# GPS_Shield.net
KiCad netlist of a schematic drawn in EAGLE
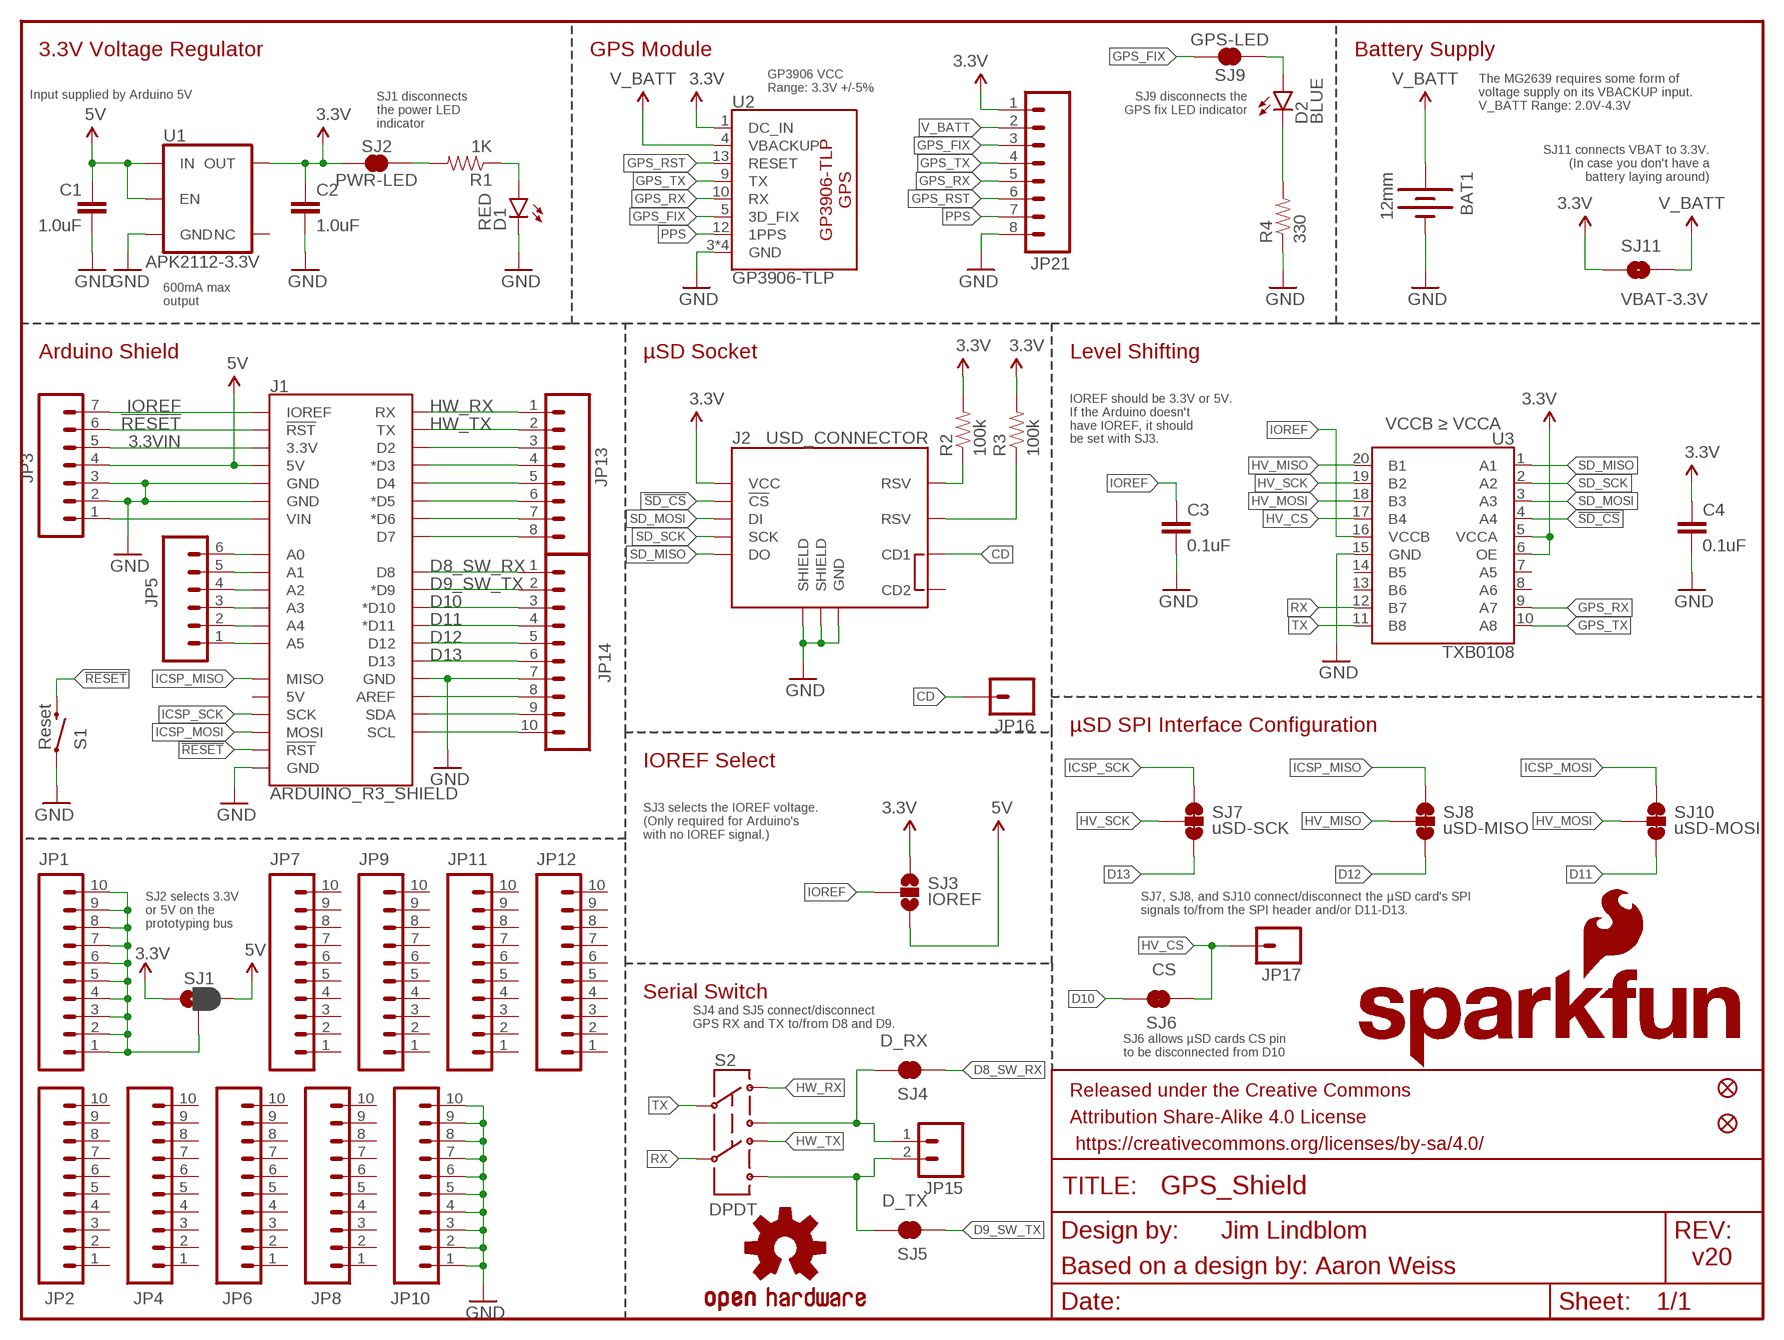
[diagram p0: schematic, sheet 1]

(export (version "E")
  (design (tool "Eeschema 10.0.6"))
  (components
    (comp (ref "BAT1")
      (value "12mm")
      (footprint "eagle-import:BATTCON_12MM")
      (libsource (lib "eagle-import") (part "BATTERY12MM"))
    )
    (comp (ref "C1")
      (value "1.0uF")
      (footprint "eagle-import:0603-CAP")
      (libsource (lib "eagle-import") (part "1.0UF-16V-10%(0603)"))
    )
    (comp (ref "C2")
      (value "1.0uF")
      (footprint "eagle-import:0603-CAP")
      (libsource (lib "eagle-import") (part "1.0UF-16V-10%(0603)"))
    )
    (comp (ref "C3")
      (value "0.1uF")
      (footprint "eagle-import:0603-CAP")
      (libsource (lib "eagle-import") (part "0.1UF-25V(+80/-20%)(0603)"))
    )
    (comp (ref "C4")
      (value "0.1uF")
      (footprint "eagle-import:0603-CAP")
      (libsource (lib "eagle-import") (part "0.1UF-25V(+80/-20%)(0603)"))
    )
    (comp (ref "D1")
      (value "RED")
      (footprint "eagle-import:LED-0603")
      (libsource (lib "eagle-import") (part "LED-RED0603"))
    )
    (comp (ref "D2")
      (value "BLUE")
      (footprint "eagle-import:LED-0603")
      (libsource (lib "eagle-import") (part "LED-BLUE0603"))
    )
    (comp (ref "FRAME1")
      (value "FRAME-LETTER")
      (footprint "eagle-import:CREATIVE_COMMONS")
      (libsource (lib "eagle-import") (part "FRAME-LETTER"))
    )
    (comp (ref "J1")
      (value "ARDUINO_R3_SHIELD")
      (footprint "eagle-import:UNO_R3_SHIELD_ICSP_NOLABELS")
      (libsource (lib "eagle-import") (part "ARDUINO_R3_SHIELD_ICSP-NO_LABELS"))
    )
    (comp (ref "J2")
      (value "USD_CONNECTOR")
      (footprint "eagle-import:MICRO-SD-SOCKET-PP")
      (libsource (lib "eagle-import") (part "USD_CONNECTOR"))
    )
    (comp (ref "JP1")
      (value "M10NO_SILK_PTH_FEMALE")
      (footprint "eagle-import:1X10_NO_SILK")
      (libsource (lib "eagle-import") (part "M10NO_SILK_PTH_FEMALE"))
    )
    (comp (ref "JP2")
      (value "M10NO_SILK_PTH_FEMALE")
      (footprint "eagle-import:1X10_NO_SILK")
      (libsource (lib "eagle-import") (part "M10NO_SILK_PTH_FEMALE"))
    )
    (comp (ref "JP3")
      (value "M07NO_SILK")
      (footprint "eagle-import:1X07_NO_SILK")
      (libsource (lib "eagle-import") (part "M07NO_SILK"))
    )
    (comp (ref "JP4")
      (value "M10NO_SILK_PTH_FEMALE")
      (footprint "eagle-import:1X10_NO_SILK")
      (libsource (lib "eagle-import") (part "M10NO_SILK_PTH_FEMALE"))
    )
    (comp (ref "JP5")
      (value "M06NO_SILK_FEMALE_PTH")
      (footprint "eagle-import:1X06_NO_SILK")
      (libsource (lib "eagle-import") (part "M06NO_SILK_FEMALE_PTH"))
    )
    (comp (ref "JP6")
      (value "M10NO_SILK_PTH_FEMALE")
      (footprint "eagle-import:1X10_NO_SILK")
      (libsource (lib "eagle-import") (part "M10NO_SILK_PTH_FEMALE"))
    )
    (comp (ref "JP7")
      (value "M10NO_SILK_PTH_FEMALE")
      (footprint "eagle-import:1X10_NO_SILK")
      (libsource (lib "eagle-import") (part "M10NO_SILK_PTH_FEMALE"))
    )
    (comp (ref "JP8")
      (value "M10NO_SILK_PTH_FEMALE")
      (footprint "eagle-import:1X10_NO_SILK")
      (libsource (lib "eagle-import") (part "M10NO_SILK_PTH_FEMALE"))
    )
    (comp (ref "JP9")
      (value "M10NO_SILK_PTH_FEMALE")
      (footprint "eagle-import:1X10_NO_SILK")
      (libsource (lib "eagle-import") (part "M10NO_SILK_PTH_FEMALE"))
    )
    (comp (ref "JP10")
      (value "M10NO_SILK_PTH_FEMALE")
      (footprint "eagle-import:1X10_NO_SILK")
      (libsource (lib "eagle-import") (part "M10NO_SILK_PTH_FEMALE"))
    )
    (comp (ref "JP11")
      (value "M10NO_SILK_PTH_FEMALE")
      (footprint "eagle-import:1X10_NO_SILK")
      (libsource (lib "eagle-import") (part "M10NO_SILK_PTH_FEMALE"))
    )
    (comp (ref "JP12")
      (value "M10NO_SILK_PTH_FEMALE")
      (footprint "eagle-import:1X10_NO_SILK")
      (libsource (lib "eagle-import") (part "M10NO_SILK_PTH_FEMALE"))
    )
    (comp (ref "JP13")
      (value "M08NO_SILK_FEMALE_PTH")
      (footprint "eagle-import:1X08_NO_SILK")
      (libsource (lib "eagle-import") (part "M08NO_SILK_FEMALE_PTH"))
    )
    (comp (ref "JP14")
      (value "M10NO_SILK_PTH_FEMALE")
      (footprint "eagle-import:1X10_NO_SILK")
      (libsource (lib "eagle-import") (part "M10NO_SILK_PTH_FEMALE"))
    )
    (comp (ref "JP15")
      (value "M021X02_NO_SILK")
      (footprint "eagle-import:1X02_NO_SILK")
      (libsource (lib "eagle-import") (part "M021X02_NO_SILK"))
    )
    (comp (ref "JP16")
      (value "M01PTH_NO_SILK_YES_STOP")
      (footprint "eagle-import:1X01_NO_SILK")
      (libsource (lib "eagle-import") (part "M01PTH_NO_SILK_YES_STOP"))
    )
    (comp (ref "JP17")
      (value "M01PTH_NO_SILK_YES_STOP")
      (footprint "eagle-import:1X01_NO_SILK")
      (libsource (lib "eagle-import") (part "M01PTH_NO_SILK_YES_STOP"))
    )
    (comp (ref "JP19")
      (value "FIDUCIAL1X2")
      (footprint "eagle-import:FIDUCIAL-1X2")
      (libsource (lib "eagle-import") (part "FIDUCIAL1X2"))
    )
    (comp (ref "JP20")
      (value "FIDUCIAL1X2")
      (footprint "eagle-import:FIDUCIAL-1X2")
      (libsource (lib "eagle-import") (part "FIDUCIAL1X2"))
    )
    (comp (ref "JP21")
      (value "M08NO_SILK_FEMALE_PTH")
      (footprint "eagle-import:1X08_NO_SILK")
      (libsource (lib "eagle-import") (part "M08NO_SILK_FEMALE_PTH"))
    )
    (comp (ref "LOGO1")
      (value "OSHW-LOGOM")
      (footprint "eagle-import:OSHW-LOGO-M")
      (libsource (lib "eagle-import") (part "OSHW-LOGOM"))
    )
    (comp (ref "LOGO2")
      (value "SFE_LOGO_NAME_FLAME.1_INCH")
      (footprint "eagle-import:SFE_LOGO_NAME_FLAME_.1")
      (libsource (lib "eagle-import") (part "SFE_LOGO_NAME_FLAME.1_INCH"))
    )
    (comp (ref "R1")
      (value "1K")
      (footprint "eagle-import:0603-RES")
      (libsource (lib "eagle-import") (part "1KOHM-1/10W-1%(0603)"))
    )
    (comp (ref "R2")
      (value "100k")
      (footprint "eagle-import:0603-RES")
      (libsource (lib "eagle-import") (part "100KOHM-1/10W-1%(0603)"))
    )
    (comp (ref "R3")
      (value "100k")
      (footprint "eagle-import:0603-RES")
      (libsource (lib "eagle-import") (part "100KOHM-1/10W-1%(0603)"))
    )
    (comp (ref "R4")
      (value "330")
      (footprint "eagle-import:0603-RES")
      (libsource (lib "eagle-import") (part "330OHM1/10W1%(0603)"))
    )
    (comp (ref "S1")
      (value "Reset")
      (footprint "eagle-import:TACTILE-SWITCH-SMD")
      (libsource (lib "eagle-import") (part "SWITCH-MOMENTARY-2SMD"))
    )
    (comp (ref "S2")
      (value "DPDT")
      (footprint "eagle-import:AYZ0202")
      (libsource (lib "eagle-import") (part "SWITCH-DPDTAYZ0202"))
    )
    (comp (ref "SJ1")
      (value "JUMPER-PAD-3-2OF3_NC_BY_PASTE")
      (footprint "eagle-import:PAD-JUMPER-3-2OF3_NC_BY_PASTE_YES_SILK_FULL_BOX")
      (libsource (lib "eagle-import") (part "JUMPER-PAD-3-2OF3_NC_BY_PASTE"))
    )
    (comp (ref "SJ2")
      (value "PWR-LED")
      (footprint "eagle-import:PAD-JUMPER-2-NC_BY_TRACE_YES_SILK")
      (libsource (lib "eagle-import") (part "JUMPER-PAD-2-NC_BY_TRACE"))
    )
    (comp (ref "SJ3")
      (value "IOREF")
      (footprint "eagle-import:PAD-JUMPER-3-NO_YES_SILK")
      (libsource (lib "eagle-import") (part "JUMPER-PAD-3-NOYES_SILK"))
    )
    (comp (ref "SJ4")
      (value "D_RX")
      (footprint "eagle-import:PAD-JUMPER-2-NC_BY_TRACE_YES_SILK")
      (libsource (lib "eagle-import") (part "JUMPER-PAD-2-NC_BY_TRACE"))
    )
    (comp (ref "SJ5")
      (value "D_TX")
      (footprint "eagle-import:PAD-JUMPER-2-NC_BY_TRACE_YES_SILK")
      (libsource (lib "eagle-import") (part "JUMPER-PAD-2-NC_BY_TRACE"))
    )
    (comp (ref "SJ6")
      (value "CS")
      (footprint "eagle-import:PAD-JUMPER-2-NC_BY_TRACE_YES_SILK")
      (libsource (lib "eagle-import") (part "JUMPER-PAD-2-NC_BY_TRACE"))
    )
    (comp (ref "SJ7")
      (value "uSD-SCK")
      (footprint "eagle-import:PAD-JUMPER-3-3OF3_NC_BY_TRACE_YES_SILK_FULL_BOX")
      (libsource (lib "eagle-import") (part "JUMPER-PAD-3-NC_BY_TRACE"))
    )
    (comp (ref "SJ8")
      (value "uSD-MISO")
      (footprint "eagle-import:PAD-JUMPER-3-3OF3_NC_BY_TRACE_YES_SILK_FULL_BOX")
      (libsource (lib "eagle-import") (part "JUMPER-PAD-3-NC_BY_TRACE"))
    )
    (comp (ref "SJ9")
      (value "GPS-LED")
      (footprint "eagle-import:PAD-JUMPER-2-NC_BY_TRACE_YES_SILK")
      (libsource (lib "eagle-import") (part "JUMPER-PAD-2-NC_BY_TRACE"))
    )
    (comp (ref "SJ10")
      (value "uSD-MOSI")
      (footprint "eagle-import:PAD-JUMPER-3-3OF3_NC_BY_TRACE_YES_SILK_FULL_BOX")
      (libsource (lib "eagle-import") (part "JUMPER-PAD-3-NC_BY_TRACE"))
    )
    (comp (ref "SJ11")
      (value "VBAT-3.3V")
      (footprint "eagle-import:PAD-JUMPER-2-NO_YES_SILK")
      (libsource (lib "eagle-import") (part "JUMPER-PAD-2-NOYES_SILK"))
    )
    (comp (ref "U1")
      (value "APK2112-3.3V")
      (footprint "eagle-import:SOT23-5")
      (libsource (lib "eagle-import") (part "V_REG_AP2112K-3.3V"))
    )
    (comp (ref "U2")
      (value "GP3906-TLP")
      (footprint "eagle-import:GP3906-TLP")
      (libsource (lib "eagle-import") (part "GP3906-TLP"))
    )
    (comp (ref "U3")
      (value "TXB0108")
      (footprint "eagle-import:UFDFN-20")
      (libsource (lib "eagle-import") (part "TXB0108"))
    )
  )
  (nets
    (net (code "1") (name "/3.3VIN") (class "Default")
      (node (ref "J1") (pin "3.3V") (pinfunction "3.3V_3.3V") (pintype "bidirectional"))
      (node (ref "JP3") (pin "5") (pinfunction "5_5") (pintype "passive"))
    )
    (net (code "2") (name "/~{RESET}") (class "Default")
      (node (ref "J1") (pin "RES") (pinfunction "~{RST}_RES") (pintype "bidirectional"))
      (node (ref "J1") (pin "RST_ICSP") (pinfunction "~{RST}_RST_ICSP") (pintype "bidirectional"))
      (node (ref "JP3") (pin "6") (pinfunction "6_6") (pintype "passive"))
      (node (ref "S1") (pin "3") (pinfunction "2_3") (pintype "passive"))
    )
    (net (code "3") (name "/~{SD_CS}") (class "Default")
      (node (ref "J2") (pin "CS") (pinfunction "~{CS}_CS") (pintype "bidirectional"))
      (node (ref "U3") (pin "4") (pinfunction "A4_4") (pintype "bidirectional"))
    )
    (net (code "4") (name "3.3V") (class "Default")
      (node (ref "C2") (pin "1") (pinfunction "1_1") (pintype "passive"))
      (node (ref "C4") (pin "1") (pinfunction "1_1") (pintype "passive"))
      (node (ref "J2") (pin "VCC") (pinfunction "VCC_VCC") (pintype "bidirectional"))
      (node (ref "JP21") (pin "1") (pinfunction "1_1") (pintype "passive"))
      (node (ref "R2") (pin "2") (pinfunction "2_2") (pintype "passive"))
      (node (ref "R3") (pin "2") (pinfunction "2_2") (pintype "passive"))
      (node (ref "SJ1") (pin "1") (pinfunction "1_1") (pintype "passive"))
      (node (ref "SJ11") (pin "1") (pinfunction "1_1") (pintype "passive"))
      (node (ref "SJ2") (pin "1") (pinfunction "1_1") (pintype "passive"))
      (node (ref "SJ3") (pin "1") (pinfunction "1_1") (pintype "passive"))
      (node (ref "U1") (pin "5") (pinfunction "OUT_5") (pintype "passive"))
      (node (ref "U2") (pin "1") (pinfunction "DC_IN_1") (pintype "bidirectional"))
      (node (ref "U3") (pin "5") (pinfunction "VCCA_5") (pintype "bidirectional"))
      (node (ref "U3") (pin "6") (pinfunction "OE_6") (pintype "bidirectional"))
    )
    (net (code "5") (name "5V") (class "Default")
      (node (ref "C1") (pin "1") (pinfunction "1_1") (pintype "passive"))
      (node (ref "J1") (pin "5V") (pinfunction "5V_5V") (pintype "bidirectional"))
      (node (ref "JP3") (pin "4") (pinfunction "4_4") (pintype "passive"))
      (node (ref "SJ1") (pin "3") (pinfunction "3_3") (pintype "passive"))
      (node (ref "SJ3") (pin "3") (pinfunction "3_3") (pintype "passive"))
      (node (ref "U1") (pin "1") (pinfunction "IN_1") (pintype "input"))
      (node (ref "U1") (pin "3") (pinfunction "EN_3") (pintype "input"))
    )
    (net (code "6") (name "CD") (class "Default")
      (node (ref "J2") (pin "CD1") (pinfunction "CD1_CD1") (pintype "bidirectional"))
      (node (ref "JP16") (pin "1") (pinfunction "1_1") (pintype "passive"))
    )
    (net (code "7") (name "D8_SW_RX") (class "Default")
      (node (ref "J1") (pin "D8") (pinfunction "D8_D8") (pintype "bidirectional"))
      (node (ref "JP14") (pin "1") (pinfunction "1_1") (pintype "passive"))
      (node (ref "SJ4") (pin "1") (pinfunction "1_1") (pintype "passive"))
    )
    (net (code "8") (name "D9_SW_TX") (class "Default")
      (node (ref "J1") (pin "D9") (pinfunction "*D9_D9") (pintype "bidirectional"))
      (node (ref "JP14") (pin "2") (pinfunction "2_2") (pintype "passive"))
      (node (ref "SJ5") (pin "1") (pinfunction "1_1") (pintype "passive"))
    )
    (net (code "9") (name "D10") (class "Default")
      (node (ref "J1") (pin "D10") (pinfunction "*D10_D10") (pintype "bidirectional"))
      (node (ref "JP14") (pin "3") (pinfunction "3_3") (pintype "passive"))
      (node (ref "SJ6") (pin "2") (pinfunction "2_2") (pintype "passive"))
    )
    (net (code "10") (name "D11") (class "Default")
      (node (ref "J1") (pin "D11") (pinfunction "*D11_D11") (pintype "bidirectional"))
      (node (ref "JP14") (pin "4") (pinfunction "4_4") (pintype "passive"))
      (node (ref "SJ10") (pin "3") (pinfunction "3_3") (pintype "passive"))
    )
    (net (code "11") (name "D12") (class "Default")
      (node (ref "J1") (pin "D12") (pinfunction "D12_D12") (pintype "bidirectional"))
      (node (ref "JP14") (pin "5") (pinfunction "5_5") (pintype "passive"))
      (node (ref "SJ8") (pin "3") (pinfunction "3_3") (pintype "passive"))
    )
    (net (code "12") (name "D13") (class "Default")
      (node (ref "J1") (pin "D13") (pinfunction "D13_D13") (pintype "bidirectional"))
      (node (ref "JP14") (pin "6") (pinfunction "6_6") (pintype "passive"))
      (node (ref "SJ7") (pin "3") (pinfunction "3_3") (pintype "passive"))
    )
    (net (code "13") (name "GND") (class "Default")
      (node (ref "BAT1") (pin "GND") (pinfunction "-_GND") (pintype "power_in"))
      (node (ref "C1") (pin "2") (pinfunction "2_2") (pintype "passive"))
      (node (ref "C2") (pin "2") (pinfunction "2_2") (pintype "passive"))
      (node (ref "C3") (pin "2") (pinfunction "2_2") (pintype "passive"))
      (node (ref "C4") (pin "2") (pinfunction "2_2") (pintype "passive"))
      (node (ref "D1") (pin "C") (pinfunction "C_C") (pintype "passive"))
      (node (ref "J1") (pin "GND@0") (pinfunction "GND_GND@0") (pintype "bidirectional"))
      (node (ref "J1") (pin "GND@1") (pinfunction "GND_GND@1") (pintype "bidirectional"))
      (node (ref "J1") (pin "GND@2") (pinfunction "GND_GND@2") (pintype "bidirectional"))
      (node (ref "J1") (pin "GND_ICSP") (pinfunction "GND_GND_ICSP") (pintype "bidirectional"))
      (node (ref "J2") (pin "GND") (pinfunction "GND_GND") (pintype "bidirectional"))
      (node (ref "J2") (pin "GND1") (pinfunction "SHIELD_GND1") (pintype "bidirectional"))
      (node (ref "J2") (pin "GND3") (pinfunction "SHIELD_GND3") (pintype "bidirectional"))
      (node (ref "JP10") (pin "1") (pinfunction "1_1") (pintype "passive"))
      (node (ref "JP10") (pin "10") (pinfunction "10_10") (pintype "passive"))
      (node (ref "JP10") (pin "2") (pinfunction "2_2") (pintype "passive"))
      (node (ref "JP10") (pin "3") (pinfunction "3_3") (pintype "passive"))
      (node (ref "JP10") (pin "4") (pinfunction "4_4") (pintype "passive"))
      (node (ref "JP10") (pin "5") (pinfunction "5_5") (pintype "passive"))
      (node (ref "JP10") (pin "6") (pinfunction "6_6") (pintype "passive"))
      (node (ref "JP10") (pin "7") (pinfunction "7_7") (pintype "passive"))
      (node (ref "JP10") (pin "8") (pinfunction "8_8") (pintype "passive"))
      (node (ref "JP10") (pin "9") (pinfunction "9_9") (pintype "passive"))
      (node (ref "JP14") (pin "7") (pinfunction "7_7") (pintype "passive"))
      (node (ref "JP21") (pin "8") (pinfunction "8_8") (pintype "passive"))
      (node (ref "JP3") (pin "2") (pinfunction "2_2") (pintype "passive"))
      (node (ref "JP3") (pin "3") (pinfunction "3_3") (pintype "passive"))
      (node (ref "R4") (pin "1") (pinfunction "1_1") (pintype "passive"))
      (node (ref "S1") (pin "1") (pinfunction "1_1") (pintype "passive"))
      (node (ref "U1") (pin "2") (pinfunction "GND_2") (pintype "input"))
      (node (ref "U2") (pin "11") (pinfunction "GND_11") (pintype "bidirectional"))
      (node (ref "U2") (pin "20") (pinfunction "GND_20") (pintype "bidirectional"))
      (node (ref "U2") (pin "3") (pinfunction "GND_3") (pintype "bidirectional"))
      (node (ref "U2") (pin "8") (pinfunction "GND_8") (pintype "bidirectional"))
      (node (ref "U3") (pin "15") (pinfunction "GND_15") (pintype "bidirectional"))
    )
    (net (code "14") (name "GPS_FIX") (class "Default")
      (node (ref "JP21") (pin "3") (pinfunction "3_3") (pintype "passive"))
      (node (ref "SJ9") (pin "2") (pinfunction "2_2") (pintype "passive"))
      (node (ref "U2") (pin "5") (pinfunction "3D_FIX_5") (pintype "bidirectional"))
    )
    (net (code "15") (name "GPS_RST") (class "Default")
      (node (ref "JP21") (pin "6") (pinfunction "6_6") (pintype "passive"))
      (node (ref "U2") (pin "13") (pinfunction "RESET_13") (pintype "bidirectional"))
    )
    (net (code "16") (name "GPS_RX") (class "Default")
      (node (ref "JP21") (pin "5") (pinfunction "5_5") (pintype "passive"))
      (node (ref "U2") (pin "10") (pinfunction "RX_10") (pintype "bidirectional"))
      (node (ref "U3") (pin "9") (pinfunction "A7_9") (pintype "bidirectional"))
    )
    (net (code "17") (name "GPS_TX") (class "Default")
      (node (ref "JP21") (pin "4") (pinfunction "4_4") (pintype "passive"))
      (node (ref "U2") (pin "9") (pinfunction "TX_9") (pintype "bidirectional"))
      (node (ref "U3") (pin "10") (pinfunction "A8_10") (pintype "bidirectional"))
    )
    (net (code "18") (name "HV_CS") (class "Default")
      (node (ref "JP17") (pin "1") (pinfunction "1_1") (pintype "passive"))
      (node (ref "SJ6") (pin "1") (pinfunction "1_1") (pintype "passive"))
      (node (ref "U3") (pin "17") (pinfunction "B4_17") (pintype "bidirectional"))
    )
    (net (code "19") (name "HV_MISO") (class "Default")
      (node (ref "SJ8") (pin "2") (pinfunction "2_2") (pintype "passive"))
      (node (ref "U3") (pin "20") (pinfunction "B1_20") (pintype "bidirectional"))
    )
    (net (code "20") (name "HV_MOSI") (class "Default")
      (node (ref "SJ10") (pin "2") (pinfunction "2_2") (pintype "passive"))
      (node (ref "U3") (pin "18") (pinfunction "B3_18") (pintype "bidirectional"))
    )
    (net (code "21") (name "HV_SCK") (class "Default")
      (node (ref "SJ7") (pin "2") (pinfunction "2_2") (pintype "passive"))
      (node (ref "U3") (pin "19") (pinfunction "B2_19") (pintype "bidirectional"))
    )
    (net (code "22") (name "HW_RX") (class "Default")
      (node (ref "J1") (pin "RX") (pinfunction "RX_RX") (pintype "bidirectional"))
      (node (ref "JP13") (pin "1") (pinfunction "1_1") (pintype "passive"))
      (node (ref "S2") (pin "1") (pinfunction "1_1") (pintype "bidirectional"))
    )
    (net (code "23") (name "HW_TX") (class "Default")
      (node (ref "J1") (pin "TX") (pinfunction "TX_TX") (pintype "bidirectional"))
      (node (ref "JP13") (pin "2") (pinfunction "2_2") (pintype "passive"))
      (node (ref "S2") (pin "4") (pinfunction "4_4") (pintype "bidirectional"))
    )
    (net (code "24") (name "ICSP_MISO") (class "Default")
      (node (ref "J1") (pin "MISO") (pinfunction "MISO_MISO") (pintype "bidirectional"))
      (node (ref "SJ8") (pin "1") (pinfunction "1_1") (pintype "passive"))
    )
    (net (code "25") (name "ICSP_MOSI") (class "Default")
      (node (ref "J1") (pin "MOSI") (pinfunction "MOSI_MOSI") (pintype "bidirectional"))
      (node (ref "SJ10") (pin "1") (pinfunction "1_1") (pintype "passive"))
    )
    (net (code "26") (name "ICSP_SCK") (class "Default")
      (node (ref "J1") (pin "SCK") (pinfunction "SCK_SCK") (pintype "bidirectional"))
      (node (ref "SJ7") (pin "1") (pinfunction "1_1") (pintype "passive"))
    )
    (net (code "27") (name "IOREF") (class "Default")
      (node (ref "C3") (pin "1") (pinfunction "1_1") (pintype "passive"))
      (node (ref "J1") (pin "IOREF") (pinfunction "IOREF_IOREF") (pintype "bidirectional"))
      (node (ref "JP3") (pin "7") (pinfunction "7_7") (pintype "passive"))
      (node (ref "SJ3") (pin "2") (pinfunction "2_2") (pintype "passive"))
      (node (ref "U3") (pin "16") (pinfunction "VCCB_16") (pintype "bidirectional"))
    )
    (net (code "28") (name "Net-(D1-PadA)") (class "Default")
      (node (ref "D1") (pin "A") (pinfunction "A_A") (pintype "passive"))
      (node (ref "R1") (pin "1") (pinfunction "1_1") (pintype "passive"))
    )
    (net (code "29") (name "Net-(D2-PadA)") (class "Default")
      (node (ref "D2") (pin "A") (pinfunction "A_A") (pintype "passive"))
      (node (ref "SJ9") (pin "1") (pinfunction "1_1") (pintype "passive"))
    )
    (net (code "30") (name "Net-(D2-PadC)") (class "Default")
      (node (ref "D2") (pin "C") (pinfunction "C_C") (pintype "passive"))
      (node (ref "R4") (pin "2") (pinfunction "2_2") (pintype "passive"))
    )
    (net (code "31") (name "Net-(J1-*D3)") (class "Default")
      (node (ref "J1") (pin "D3") (pinfunction "*D3_D3") (pintype "bidirectional"))
      (node (ref "JP13") (pin "4") (pinfunction "4_4") (pintype "passive"))
    )
    (net (code "32") (name "Net-(J1-*D5)") (class "Default")
      (node (ref "J1") (pin "D5") (pinfunction "*D5_D5") (pintype "bidirectional"))
      (node (ref "JP13") (pin "6") (pinfunction "6_6") (pintype "passive"))
    )
    (net (code "33") (name "Net-(J1-*D6)") (class "Default")
      (node (ref "J1") (pin "D6") (pinfunction "*D6_D6") (pintype "bidirectional"))
      (node (ref "JP13") (pin "7") (pinfunction "7_7") (pintype "passive"))
    )
    (net (code "34") (name "Net-(J1-PadA0)") (class "Default")
      (node (ref "J1") (pin "A0") (pinfunction "A0_A0") (pintype "bidirectional"))
      (node (ref "JP5") (pin "6") (pinfunction "6_6") (pintype "passive"))
    )
    (net (code "35") (name "Net-(J1-PadA1)") (class "Default")
      (node (ref "J1") (pin "A1") (pinfunction "A1_A1") (pintype "bidirectional"))
      (node (ref "JP5") (pin "5") (pinfunction "5_5") (pintype "passive"))
    )
    (net (code "36") (name "Net-(J1-PadA2)") (class "Default")
      (node (ref "J1") (pin "A2") (pinfunction "A2_A2") (pintype "bidirectional"))
      (node (ref "JP5") (pin "4") (pinfunction "4_4") (pintype "passive"))
    )
    (net (code "37") (name "Net-(J1-PadA3)") (class "Default")
      (node (ref "J1") (pin "A3") (pinfunction "A3_A3") (pintype "bidirectional"))
      (node (ref "JP5") (pin "3") (pinfunction "3_3") (pintype "passive"))
    )
    (net (code "38") (name "Net-(J1-PadA4)") (class "Default")
      (node (ref "J1") (pin "A4") (pinfunction "A4_A4") (pintype "bidirectional"))
      (node (ref "JP5") (pin "2") (pinfunction "2_2") (pintype "passive"))
    )
    (net (code "39") (name "Net-(J1-PadA5)") (class "Default")
      (node (ref "J1") (pin "A5") (pinfunction "A5_A5") (pintype "bidirectional"))
      (node (ref "JP5") (pin "1") (pinfunction "1_1") (pintype "passive"))
    )
    (net (code "40") (name "Net-(J1-PadAREF)") (class "Default")
      (node (ref "J1") (pin "AREF") (pinfunction "AREF_AREF") (pintype "bidirectional"))
      (node (ref "JP14") (pin "8") (pinfunction "8_8") (pintype "passive"))
    )
    (net (code "41") (name "Net-(J1-PadD2)") (class "Default")
      (node (ref "J1") (pin "D2") (pinfunction "D2_D2") (pintype "bidirectional"))
      (node (ref "JP13") (pin "3") (pinfunction "3_3") (pintype "passive"))
    )
    (net (code "42") (name "Net-(J1-PadD4)") (class "Default")
      (node (ref "J1") (pin "D4") (pinfunction "D4_D4") (pintype "bidirectional"))
      (node (ref "JP13") (pin "5") (pinfunction "5_5") (pintype "passive"))
    )
    (net (code "43") (name "Net-(J1-PadD7)") (class "Default")
      (node (ref "J1") (pin "D7") (pinfunction "D7_D7") (pintype "bidirectional"))
      (node (ref "JP13") (pin "8") (pinfunction "8_8") (pintype "passive"))
    )
    (net (code "44") (name "Net-(J1-PadSCL)") (class "Default")
      (node (ref "J1") (pin "SCL") (pinfunction "SCL_SCL") (pintype "bidirectional"))
      (node (ref "JP14") (pin "10") (pinfunction "10_10") (pintype "passive"))
    )
    (net (code "45") (name "Net-(J1-PadSDA)") (class "Default")
      (node (ref "J1") (pin "SDA") (pinfunction "SDA_SDA") (pintype "bidirectional"))
      (node (ref "JP14") (pin "9") (pinfunction "9_9") (pintype "passive"))
    )
    (net (code "46") (name "Net-(J1-PadVIN)") (class "Default")
      (node (ref "J1") (pin "VIN") (pinfunction "VIN_VIN") (pintype "bidirectional"))
      (node (ref "JP3") (pin "1") (pinfunction "1_1") (pintype "passive"))
    )
    (net (code "47") (name "Net-(J2-RSV-PadRSV1)") (class "Default")
      (node (ref "J2") (pin "RSV1") (pinfunction "RSV_RSV1") (pintype "bidirectional"))
      (node (ref "R2") (pin "1") (pinfunction "1_1") (pintype "passive"))
    )
    (net (code "48") (name "Net-(J2-RSV-PadRSV2)") (class "Default")
      (node (ref "J2") (pin "RSV2") (pinfunction "RSV_RSV2") (pintype "bidirectional"))
      (node (ref "R3") (pin "1") (pinfunction "1_1") (pintype "passive"))
    )
    (net (code "49") (name "Net-(JP1-Pad1)") (class "Default")
      (node (ref "JP1") (pin "1") (pinfunction "1_1") (pintype "passive"))
      (node (ref "JP1") (pin "10") (pinfunction "10_10") (pintype "passive"))
      (node (ref "JP1") (pin "2") (pinfunction "2_2") (pintype "passive"))
      (node (ref "JP1") (pin "3") (pinfunction "3_3") (pintype "passive"))
      (node (ref "JP1") (pin "4") (pinfunction "4_4") (pintype "passive"))
      (node (ref "JP1") (pin "5") (pinfunction "5_5") (pintype "passive"))
      (node (ref "JP1") (pin "6") (pinfunction "6_6") (pintype "passive"))
      (node (ref "JP1") (pin "7") (pinfunction "7_7") (pintype "passive"))
      (node (ref "JP1") (pin "8") (pinfunction "8_8") (pintype "passive"))
      (node (ref "JP1") (pin "9") (pinfunction "9_9") (pintype "passive"))
      (node (ref "SJ1") (pin "2") (pinfunction "2_2") (pintype "passive"))
    )
    (net (code "50") (name "Net-(JP15-Pad1)") (class "Default")
      (node (ref "JP15") (pin "1") (pinfunction "1_1") (pintype "passive"))
      (node (ref "S2") (pin "3") (pinfunction "3_3") (pintype "bidirectional"))
      (node (ref "SJ4") (pin "2") (pinfunction "2_2") (pintype "passive"))
    )
    (net (code "51") (name "Net-(JP15-Pad2)") (class "Default")
      (node (ref "JP15") (pin "2") (pinfunction "2_2") (pintype "passive"))
      (node (ref "S2") (pin "6") (pinfunction "6_6") (pintype "bidirectional"))
      (node (ref "SJ5") (pin "2") (pinfunction "2_2") (pintype "passive"))
    )
    (net (code "52") (name "Net-(R1-Pad2)") (class "Default")
      (node (ref "R1") (pin "2") (pinfunction "2_2") (pintype "passive"))
      (node (ref "SJ2") (pin "2") (pinfunction "2_2") (pintype "passive"))
    )
    (net (code "53") (name "PPS") (class "Default")
      (node (ref "JP21") (pin "7") (pinfunction "7_7") (pintype "passive"))
      (node (ref "U2") (pin "12") (pinfunction "1PPS_12") (pintype "bidirectional"))
    )
    (net (code "54") (name "RX") (class "Default")
      (node (ref "S2") (pin "5") (pinfunction "5_5") (pintype "bidirectional"))
      (node (ref "U3") (pin "12") (pinfunction "B7_12") (pintype "bidirectional"))
    )
    (net (code "55") (name "SD_MISO") (class "Default")
      (node (ref "J2") (pin "DO") (pinfunction "DO_DO") (pintype "bidirectional"))
      (node (ref "U3") (pin "1") (pinfunction "A1_1") (pintype "bidirectional"))
    )
    (net (code "56") (name "SD_MOSI") (class "Default")
      (node (ref "J2") (pin "DI") (pinfunction "DI_DI") (pintype "bidirectional"))
      (node (ref "U3") (pin "3") (pinfunction "A3_3") (pintype "bidirectional"))
    )
    (net (code "57") (name "SD_SCK") (class "Default")
      (node (ref "J2") (pin "SCLK") (pinfunction "SCK_SCLK") (pintype "bidirectional"))
      (node (ref "U3") (pin "2") (pinfunction "A2_2") (pintype "bidirectional"))
    )
    (net (code "58") (name "TX") (class "Default")
      (node (ref "S2") (pin "2") (pinfunction "2_2") (pintype "bidirectional"))
      (node (ref "U3") (pin "11") (pinfunction "B8_11") (pintype "bidirectional"))
    )
    (net (code "59") (name "V_BATT") (class "Default")
      (node (ref "BAT1") (pin "PWR@1") (pinfunction "+_PWR@1") (pintype "power_in"))
      (node (ref "JP21") (pin "2") (pinfunction "2_2") (pintype "passive"))
      (node (ref "SJ11") (pin "2") (pinfunction "2_2") (pintype "passive"))
      (node (ref "U2") (pin "4") (pinfunction "VBACKUP_4") (pintype "bidirectional"))
    )
    (net (code "60") (name "unconnected-(J1-5V-Pad5V_ICSP)") (class "Default")
      (node (ref "J1") (pin "5V_ICSP") (pinfunction "5V_5V_ICSP") (pintype "bidirectional"))
    )
    (net (code "61") (name "unconnected-(J2-PadCD2)") (class "Default")
      (node (ref "J2") (pin "CD2") (pinfunction "CD2_CD2") (pintype "bidirectional"))
    )
    (net (code "62") (name "unconnected-(JP2-Pad1)") (class "Default")
      (node (ref "JP2") (pin "1") (pinfunction "1_1") (pintype "passive"))
    )
    (net (code "63") (name "unconnected-(JP2-Pad2)") (class "Default")
      (node (ref "JP2") (pin "2") (pinfunction "2_2") (pintype "passive"))
    )
    (net (code "64") (name "unconnected-(JP2-Pad3)") (class "Default")
      (node (ref "JP2") (pin "3") (pinfunction "3_3") (pintype "passive"))
    )
    (net (code "65") (name "unconnected-(JP2-Pad4)") (class "Default")
      (node (ref "JP2") (pin "4") (pinfunction "4_4") (pintype "passive"))
    )
    (net (code "66") (name "unconnected-(JP2-Pad5)") (class "Default")
      (node (ref "JP2") (pin "5") (pinfunction "5_5") (pintype "passive"))
    )
    (net (code "67") (name "unconnected-(JP2-Pad6)") (class "Default")
      (node (ref "JP2") (pin "6") (pinfunction "6_6") (pintype "passive"))
    )
    (net (code "68") (name "unconnected-(JP2-Pad7)") (class "Default")
      (node (ref "JP2") (pin "7") (pinfunction "7_7") (pintype "passive"))
    )
    (net (code "69") (name "unconnected-(JP2-Pad8)") (class "Default")
      (node (ref "JP2") (pin "8") (pinfunction "8_8") (pintype "passive"))
    )
    (net (code "70") (name "unconnected-(JP2-Pad9)") (class "Default")
      (node (ref "JP2") (pin "9") (pinfunction "9_9") (pintype "passive"))
    )
    (net (code "71") (name "unconnected-(JP2-Pad10)") (class "Default")
      (node (ref "JP2") (pin "10") (pinfunction "10_10") (pintype "passive"))
    )
    (net (code "72") (name "unconnected-(JP4-Pad1)") (class "Default")
      (node (ref "JP4") (pin "1") (pinfunction "1_1") (pintype "passive"))
    )
    (net (code "73") (name "unconnected-(JP4-Pad2)") (class "Default")
      (node (ref "JP4") (pin "2") (pinfunction "2_2") (pintype "passive"))
    )
    (net (code "74") (name "unconnected-(JP4-Pad3)") (class "Default")
      (node (ref "JP4") (pin "3") (pinfunction "3_3") (pintype "passive"))
    )
    (net (code "75") (name "unconnected-(JP4-Pad4)") (class "Default")
      (node (ref "JP4") (pin "4") (pinfunction "4_4") (pintype "passive"))
    )
    (net (code "76") (name "unconnected-(JP4-Pad5)") (class "Default")
      (node (ref "JP4") (pin "5") (pinfunction "5_5") (pintype "passive"))
    )
    (net (code "77") (name "unconnected-(JP4-Pad6)") (class "Default")
      (node (ref "JP4") (pin "6") (pinfunction "6_6") (pintype "passive"))
    )
    (net (code "78") (name "unconnected-(JP4-Pad7)") (class "Default")
      (node (ref "JP4") (pin "7") (pinfunction "7_7") (pintype "passive"))
    )
    (net (code "79") (name "unconnected-(JP4-Pad8)") (class "Default")
      (node (ref "JP4") (pin "8") (pinfunction "8_8") (pintype "passive"))
    )
    (net (code "80") (name "unconnected-(JP4-Pad9)") (class "Default")
      (node (ref "JP4") (pin "9") (pinfunction "9_9") (pintype "passive"))
    )
    (net (code "81") (name "unconnected-(JP4-Pad10)") (class "Default")
      (node (ref "JP4") (pin "10") (pinfunction "10_10") (pintype "passive"))
    )
    (net (code "82") (name "unconnected-(JP6-Pad1)") (class "Default")
      (node (ref "JP6") (pin "1") (pinfunction "1_1") (pintype "passive"))
    )
    (net (code "83") (name "unconnected-(JP6-Pad2)") (class "Default")
      (node (ref "JP6") (pin "2") (pinfunction "2_2") (pintype "passive"))
    )
    (net (code "84") (name "unconnected-(JP6-Pad3)") (class "Default")
      (node (ref "JP6") (pin "3") (pinfunction "3_3") (pintype "passive"))
    )
    (net (code "85") (name "unconnected-(JP6-Pad4)") (class "Default")
      (node (ref "JP6") (pin "4") (pinfunction "4_4") (pintype "passive"))
    )
    (net (code "86") (name "unconnected-(JP6-Pad5)") (class "Default")
      (node (ref "JP6") (pin "5") (pinfunction "5_5") (pintype "passive"))
    )
    (net (code "87") (name "unconnected-(JP6-Pad6)") (class "Default")
      (node (ref "JP6") (pin "6") (pinfunction "6_6") (pintype "passive"))
    )
    (net (code "88") (name "unconnected-(JP6-Pad7)") (class "Default")
      (node (ref "JP6") (pin "7") (pinfunction "7_7") (pintype "passive"))
    )
    (net (code "89") (name "unconnected-(JP6-Pad8)") (class "Default")
      (node (ref "JP6") (pin "8") (pinfunction "8_8") (pintype "passive"))
    )
    (net (code "90") (name "unconnected-(JP6-Pad9)") (class "Default")
      (node (ref "JP6") (pin "9") (pinfunction "9_9") (pintype "passive"))
    )
    (net (code "91") (name "unconnected-(JP6-Pad10)") (class "Default")
      (node (ref "JP6") (pin "10") (pinfunction "10_10") (pintype "passive"))
    )
    (net (code "92") (name "unconnected-(JP7-Pad1)") (class "Default")
      (node (ref "JP7") (pin "1") (pinfunction "1_1") (pintype "passive"))
    )
    (net (code "93") (name "unconnected-(JP7-Pad2)") (class "Default")
      (node (ref "JP7") (pin "2") (pinfunction "2_2") (pintype "passive"))
    )
    (net (code "94") (name "unconnected-(JP7-Pad3)") (class "Default")
      (node (ref "JP7") (pin "3") (pinfunction "3_3") (pintype "passive"))
    )
    (net (code "95") (name "unconnected-(JP7-Pad4)") (class "Default")
      (node (ref "JP7") (pin "4") (pinfunction "4_4") (pintype "passive"))
    )
    (net (code "96") (name "unconnected-(JP7-Pad5)") (class "Default")
      (node (ref "JP7") (pin "5") (pinfunction "5_5") (pintype "passive"))
    )
    (net (code "97") (name "unconnected-(JP7-Pad6)") (class "Default")
      (node (ref "JP7") (pin "6") (pinfunction "6_6") (pintype "passive"))
    )
    (net (code "98") (name "unconnected-(JP7-Pad7)") (class "Default")
      (node (ref "JP7") (pin "7") (pinfunction "7_7") (pintype "passive"))
    )
    (net (code "99") (name "unconnected-(JP7-Pad8)") (class "Default")
      (node (ref "JP7") (pin "8") (pinfunction "8_8") (pintype "passive"))
    )
    (net (code "100") (name "unconnected-(JP7-Pad9)") (class "Default")
      (node (ref "JP7") (pin "9") (pinfunction "9_9") (pintype "passive"))
    )
    (net (code "101") (name "unconnected-(JP7-Pad10)") (class "Default")
      (node (ref "JP7") (pin "10") (pinfunction "10_10") (pintype "passive"))
    )
    (net (code "102") (name "unconnected-(JP8-Pad1)") (class "Default")
      (node (ref "JP8") (pin "1") (pinfunction "1_1") (pintype "passive"))
    )
    (net (code "103") (name "unconnected-(JP8-Pad2)") (class "Default")
      (node (ref "JP8") (pin "2") (pinfunction "2_2") (pintype "passive"))
    )
    (net (code "104") (name "unconnected-(JP8-Pad3)") (class "Default")
      (node (ref "JP8") (pin "3") (pinfunction "3_3") (pintype "passive"))
    )
    (net (code "105") (name "unconnected-(JP8-Pad4)") (class "Default")
      (node (ref "JP8") (pin "4") (pinfunction "4_4") (pintype "passive"))
    )
    (net (code "106") (name "unconnected-(JP8-Pad5)") (class "Default")
      (node (ref "JP8") (pin "5") (pinfunction "5_5") (pintype "passive"))
    )
    (net (code "107") (name "unconnected-(JP8-Pad6)") (class "Default")
      (node (ref "JP8") (pin "6") (pinfunction "6_6") (pintype "passive"))
    )
    (net (code "108") (name "unconnected-(JP8-Pad7)") (class "Default")
      (node (ref "JP8") (pin "7") (pinfunction "7_7") (pintype "passive"))
    )
    (net (code "109") (name "unconnected-(JP8-Pad8)") (class "Default")
      (node (ref "JP8") (pin "8") (pinfunction "8_8") (pintype "passive"))
    )
    (net (code "110") (name "unconnected-(JP8-Pad9)") (class "Default")
      (node (ref "JP8") (pin "9") (pinfunction "9_9") (pintype "passive"))
    )
    (net (code "111") (name "unconnected-(JP8-Pad10)") (class "Default")
      (node (ref "JP8") (pin "10") (pinfunction "10_10") (pintype "passive"))
    )
    (net (code "112") (name "unconnected-(JP9-Pad1)") (class "Default")
      (node (ref "JP9") (pin "1") (pinfunction "1_1") (pintype "passive"))
    )
    (net (code "113") (name "unconnected-(JP9-Pad2)") (class "Default")
      (node (ref "JP9") (pin "2") (pinfunction "2_2") (pintype "passive"))
    )
    (net (code "114") (name "unconnected-(JP9-Pad3)") (class "Default")
      (node (ref "JP9") (pin "3") (pinfunction "3_3") (pintype "passive"))
    )
    (net (code "115") (name "unconnected-(JP9-Pad4)") (class "Default")
      (node (ref "JP9") (pin "4") (pinfunction "4_4") (pintype "passive"))
    )
    (net (code "116") (name "unconnected-(JP9-Pad5)") (class "Default")
      (node (ref "JP9") (pin "5") (pinfunction "5_5") (pintype "passive"))
    )
    (net (code "117") (name "unconnected-(JP9-Pad6)") (class "Default")
      (node (ref "JP9") (pin "6") (pinfunction "6_6") (pintype "passive"))
    )
    (net (code "118") (name "unconnected-(JP9-Pad7)") (class "Default")
      (node (ref "JP9") (pin "7") (pinfunction "7_7") (pintype "passive"))
    )
    (net (code "119") (name "unconnected-(JP9-Pad8)") (class "Default")
      (node (ref "JP9") (pin "8") (pinfunction "8_8") (pintype "passive"))
    )
    (net (code "120") (name "unconnected-(JP9-Pad9)") (class "Default")
      (node (ref "JP9") (pin "9") (pinfunction "9_9") (pintype "passive"))
    )
    (net (code "121") (name "unconnected-(JP9-Pad10)") (class "Default")
      (node (ref "JP9") (pin "10") (pinfunction "10_10") (pintype "passive"))
    )
    (net (code "122") (name "unconnected-(JP11-Pad1)") (class "Default")
      (node (ref "JP11") (pin "1") (pinfunction "1_1") (pintype "passive"))
    )
    (net (code "123") (name "unconnected-(JP11-Pad2)") (class "Default")
      (node (ref "JP11") (pin "2") (pinfunction "2_2") (pintype "passive"))
    )
    (net (code "124") (name "unconnected-(JP11-Pad3)") (class "Default")
      (node (ref "JP11") (pin "3") (pinfunction "3_3") (pintype "passive"))
    )
    (net (code "125") (name "unconnected-(JP11-Pad4)") (class "Default")
      (node (ref "JP11") (pin "4") (pinfunction "4_4") (pintype "passive"))
    )
    (net (code "126") (name "unconnected-(JP11-Pad5)") (class "Default")
      (node (ref "JP11") (pin "5") (pinfunction "5_5") (pintype "passive"))
    )
    (net (code "127") (name "unconnected-(JP11-Pad6)") (class "Default")
      (node (ref "JP11") (pin "6") (pinfunction "6_6") (pintype "passive"))
    )
    (net (code "128") (name "unconnected-(JP11-Pad7)") (class "Default")
      (node (ref "JP11") (pin "7") (pinfunction "7_7") (pintype "passive"))
    )
    (net (code "129") (name "unconnected-(JP11-Pad8)") (class "Default")
      (node (ref "JP11") (pin "8") (pinfunction "8_8") (pintype "passive"))
    )
    (net (code "130") (name "unconnected-(JP11-Pad9)") (class "Default")
      (node (ref "JP11") (pin "9") (pinfunction "9_9") (pintype "passive"))
    )
    (net (code "131") (name "unconnected-(JP11-Pad10)") (class "Default")
      (node (ref "JP11") (pin "10") (pinfunction "10_10") (pintype "passive"))
    )
    (net (code "132") (name "unconnected-(JP12-Pad1)") (class "Default")
      (node (ref "JP12") (pin "1") (pinfunction "1_1") (pintype "passive"))
    )
    (net (code "133") (name "unconnected-(JP12-Pad2)") (class "Default")
      (node (ref "JP12") (pin "2") (pinfunction "2_2") (pintype "passive"))
    )
    (net (code "134") (name "unconnected-(JP12-Pad3)") (class "Default")
      (node (ref "JP12") (pin "3") (pinfunction "3_3") (pintype "passive"))
    )
    (net (code "135") (name "unconnected-(JP12-Pad4)") (class "Default")
      (node (ref "JP12") (pin "4") (pinfunction "4_4") (pintype "passive"))
    )
    (net (code "136") (name "unconnected-(JP12-Pad5)") (class "Default")
      (node (ref "JP12") (pin "5") (pinfunction "5_5") (pintype "passive"))
    )
    (net (code "137") (name "unconnected-(JP12-Pad6)") (class "Default")
      (node (ref "JP12") (pin "6") (pinfunction "6_6") (pintype "passive"))
    )
    (net (code "138") (name "unconnected-(JP12-Pad7)") (class "Default")
      (node (ref "JP12") (pin "7") (pinfunction "7_7") (pintype "passive"))
    )
    (net (code "139") (name "unconnected-(JP12-Pad8)") (class "Default")
      (node (ref "JP12") (pin "8") (pinfunction "8_8") (pintype "passive"))
    )
    (net (code "140") (name "unconnected-(JP12-Pad9)") (class "Default")
      (node (ref "JP12") (pin "9") (pinfunction "9_9") (pintype "passive"))
    )
    (net (code "141") (name "unconnected-(JP12-Pad10)") (class "Default")
      (node (ref "JP12") (pin "10") (pinfunction "10_10") (pintype "passive"))
    )
    (net (code "142") (name "unconnected-(U1-NC-Pad4)") (class "Default")
      (node (ref "U1") (pin "4") (pinfunction "NC_4") (pintype "input"))
    )
    (net (code "143") (name "unconnected-(U3-A5-Pad7)") (class "Default")
      (node (ref "U3") (pin "7") (pinfunction "A5_7") (pintype "bidirectional"))
    )
    (net (code "144") (name "unconnected-(U3-A6-Pad8)") (class "Default")
      (node (ref "U3") (pin "8") (pinfunction "A6_8") (pintype "bidirectional"))
    )
    (net (code "145") (name "unconnected-(U3-B5-Pad14)") (class "Default")
      (node (ref "U3") (pin "14") (pinfunction "B5_14") (pintype "bidirectional"))
    )
    (net (code "146") (name "unconnected-(U3-B6-Pad13)") (class "Default")
      (node (ref "U3") (pin "13") (pinfunction "B6_13") (pintype "bidirectional"))
    )
  )
)
